# schematic_luminosidade_controle.net
KiCad netlist of a schematic drawn in EAGLE
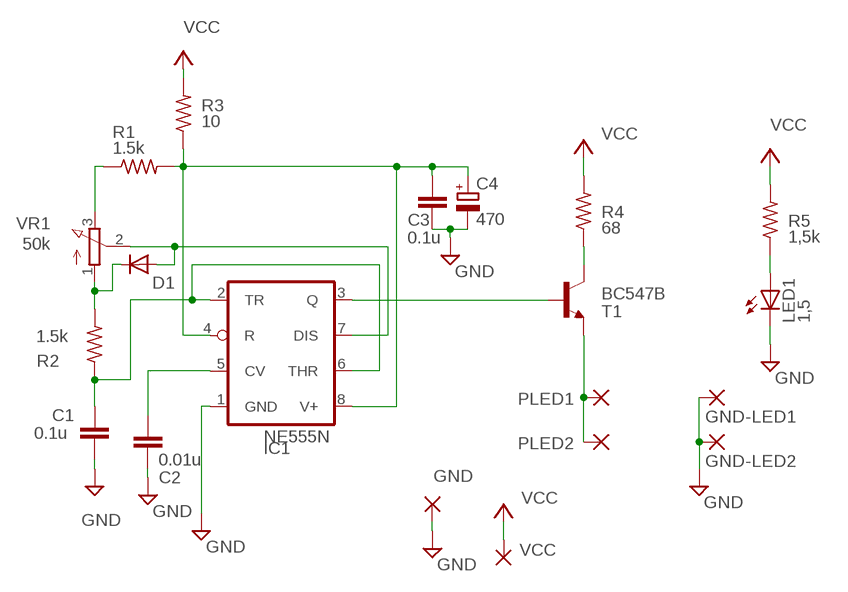
[diagram p0: schematic, sheet 1]

(export (version "E")
  (design (tool "Eeschema 10.0.6"))
  (components
    (comp (ref "C1")
      (value "0.1u")
      (footprint "eagle-import:C025-024X044")
      (libsource (lib "eagle-import") (part "C-EU025-024X044"))
    )
    (comp (ref "C2")
      (value "0.01u")
      (footprint "eagle-import:C025-024X044")
      (libsource (lib "eagle-import") (part "C-EU025-024X044"))
    )
    (comp (ref "C3")
      (value "0.1u")
      (footprint "eagle-import:C025-024X044")
      (libsource (lib "eagle-import") (part "C-EU025-024X044"))
    )
    (comp (ref "C4")
      (value "470")
      (footprint "eagle-import:E3,5-10")
      (libsource (lib "eagle-import") (part "CPOL-EUE3.5-10"))
    )
    (comp (ref "D1")
      (value "1N4148DO35-7")
      (footprint "eagle-import:DO35-7")
      (libsource (lib "eagle-import") (part "1N4148DO35-7"))
    )
    (comp (ref "GND")
      (value "ET1")
      (footprint "eagle-import:2,15_1,0")
      (libsource (lib "eagle-import") (part "2,15/1,0"))
    )
    (comp (ref "GND-LED1")
      (value "GPAD")
      (footprint "eagle-import:2,15_1,0")
      (libsource (lib "eagle-import") (part "2,15/1,0"))
    )
    (comp (ref "GND-LED2")
      (value "GPAD")
      (footprint "eagle-import:2,15_1,0")
      (libsource (lib "eagle-import") (part "2,15/1,0"))
    )
    (comp (ref "IC1")
      (value "NE555N")
      (footprint "eagle-import:DIL08")
      (libsource (lib "eagle-import") (part "555NNE"))
    )
    (comp (ref "LED1")
      (value "1,5")
      (footprint "eagle-import:LED5MM")
      (libsource (lib "eagle-import") (part "LED5MM"))
    )
    (comp (ref "PLED1")
      (value "ET1")
      (footprint "eagle-import:2,15_1,0")
      (libsource (lib "eagle-import") (part "2,15/1,0"))
    )
    (comp (ref "PLED2")
      (value "ET1")
      (footprint "eagle-import:2,15_1,0")
      (libsource (lib "eagle-import") (part "2,15/1,0"))
    )
    (comp (ref "R1")
      (value "1.5k")
      (footprint "eagle-import:0204_5")
      (libsource (lib "eagle-import") (part "R-US_0204/5"))
    )
    (comp (ref "R2")
      (value "1.5k")
      (footprint "eagle-import:0204_5")
      (libsource (lib "eagle-import") (part "R-US_0204/5"))
    )
    (comp (ref "R3")
      (value "10")
      (footprint "eagle-import:0204_5")
      (libsource (lib "eagle-import") (part "R-US_0204/5"))
    )
    (comp (ref "R4")
      (value "68")
      (footprint "eagle-import:0204_5")
      (libsource (lib "eagle-import") (part "R-US_0204/5"))
    )
    (comp (ref "R5")
      (value "1,5k")
      (footprint "eagle-import:0204_5")
      (libsource (lib "eagle-import") (part "R-US_0204/5"))
    )
    (comp (ref "T1")
      (value "BC547B")
      (footprint "eagle-import:TO92")
      (libsource (lib "eagle-import") (part "BC547B"))
    )
    (comp (ref "VCC")
      (value "ET1")
      (footprint "eagle-import:2,15_1,0")
      (libsource (lib "eagle-import") (part "2,15/1,0"))
    )
    (comp (ref "VR1")
      (value "50k")
      (footprint "eagle-import:3RP_1610N")
      (libsource (lib "eagle-import") (part "3RP/1610N"))
    )
  )
  (nets
    (net (code "1") (name "GND") (class "Default")
      (node (ref "C1") (pin "2") (pinfunction "2_2") (pintype "passive"))
      (node (ref "C2") (pin "2") (pinfunction "2_2") (pintype "passive"))
      (node (ref "C3") (pin "2") (pinfunction "2_2") (pintype "passive"))
      (node (ref "C4") (pin "-") (pinfunction "-_-") (pintype "passive"))
      (node (ref "GND") (pin "1") (pinfunction "P_1") (pintype "passive"))
      (node (ref "GND-LED1") (pin "1") (pinfunction "P_1") (pintype "passive"))
      (node (ref "GND-LED2") (pin "1") (pinfunction "P_1") (pintype "passive"))
      (node (ref "IC1") (pin "1") (pinfunction "GND_1") (pintype "power_in"))
      (node (ref "LED1") (pin "K") (pinfunction "C_K") (pintype "passive"))
    )
    (net (code "2") (name "Net-(IC1-CV)") (class "Default")
      (node (ref "C2") (pin "1") (pinfunction "1_1") (pintype "passive"))
      (node (ref "IC1") (pin "5") (pinfunction "CV_5") (pintype "input"))
    )
    (net (code "3") (name "Net-(IC1-DIS)") (class "Default")
      (node (ref "D1") (pin "A") (pinfunction "A_A") (pintype "passive"))
      (node (ref "IC1") (pin "7") (pinfunction "DIS_7") (pintype "input"))
      (node (ref "VR1") (pin "2") (pinfunction "S_2") (pintype "passive"))
    )
    (net (code "4") (name "Net-(IC1-Q)") (class "Default")
      (node (ref "IC1") (pin "3") (pinfunction "Q_3") (pintype "output"))
      (node (ref "T1") (pin "2") (pinfunction "B_2") (pintype "passive"))
    )
    (net (code "5") (name "Net-(IC1-R)") (class "Default")
      (node (ref "C3") (pin "1") (pinfunction "1_1") (pintype "passive"))
      (node (ref "C4") (pin "+") (pinfunction "+_+") (pintype "passive"))
      (node (ref "IC1") (pin "4") (pinfunction "R_4") (pintype "input"))
      (node (ref "IC1") (pin "8") (pinfunction "V+_8") (pintype "power_in"))
      (node (ref "R1") (pin "2") (pinfunction "2_2") (pintype "passive"))
      (node (ref "R3") (pin "1") (pinfunction "1_1") (pintype "passive"))
    )
    (net (code "6") (name "Net-(IC1-THR)") (class "Default")
      (node (ref "C1") (pin "1") (pinfunction "1_1") (pintype "passive"))
      (node (ref "IC1") (pin "2") (pinfunction "TR_2") (pintype "input"))
      (node (ref "IC1") (pin "6") (pinfunction "THR_6") (pintype "input"))
      (node (ref "R2") (pin "1") (pinfunction "1_1") (pintype "passive"))
    )
    (net (code "7") (name "Net-(LED1-PadA)") (class "Default")
      (node (ref "LED1") (pin "A") (pinfunction "A_A") (pintype "passive"))
      (node (ref "R5") (pin "1") (pinfunction "1_1") (pintype "passive"))
    )
    (net (code "8") (name "Net-(PLED1-P)") (class "Default")
      (node (ref "PLED1") (pin "1") (pinfunction "P_1") (pintype "passive"))
      (node (ref "PLED2") (pin "1") (pinfunction "P_1") (pintype "passive"))
      (node (ref "T1") (pin "1") (pinfunction "E_1") (pintype "passive"))
    )
    (net (code "9") (name "Net-(T1-C)") (class "Default")
      (node (ref "R4") (pin "1") (pinfunction "1_1") (pintype "passive"))
      (node (ref "T1") (pin "3") (pinfunction "C_3") (pintype "passive"))
    )
    (net (code "10") (name "Net-(VR1-A)") (class "Default")
      (node (ref "D1") (pin "C") (pinfunction "C_C") (pintype "passive"))
      (node (ref "R2") (pin "2") (pinfunction "2_2") (pintype "passive"))
      (node (ref "VR1") (pin "1") (pinfunction "A_1") (pintype "passive"))
    )
    (net (code "11") (name "Net-(VR1-E)") (class "Default")
      (node (ref "R1") (pin "1") (pinfunction "1_1") (pintype "passive"))
      (node (ref "VR1") (pin "3") (pinfunction "E_3") (pintype "passive"))
    )
    (net (code "12") (name "VCC") (class "Default")
      (node (ref "R3") (pin "2") (pinfunction "2_2") (pintype "passive"))
      (node (ref "R4") (pin "2") (pinfunction "2_2") (pintype "passive"))
      (node (ref "R5") (pin "2") (pinfunction "2_2") (pintype "passive"))
      (node (ref "VCC") (pin "1") (pinfunction "P_1") (pintype "passive"))
    )
  )
)
